# Serial_final_rev01.net
KiCad netlist of a schematic drawn in EAGLE
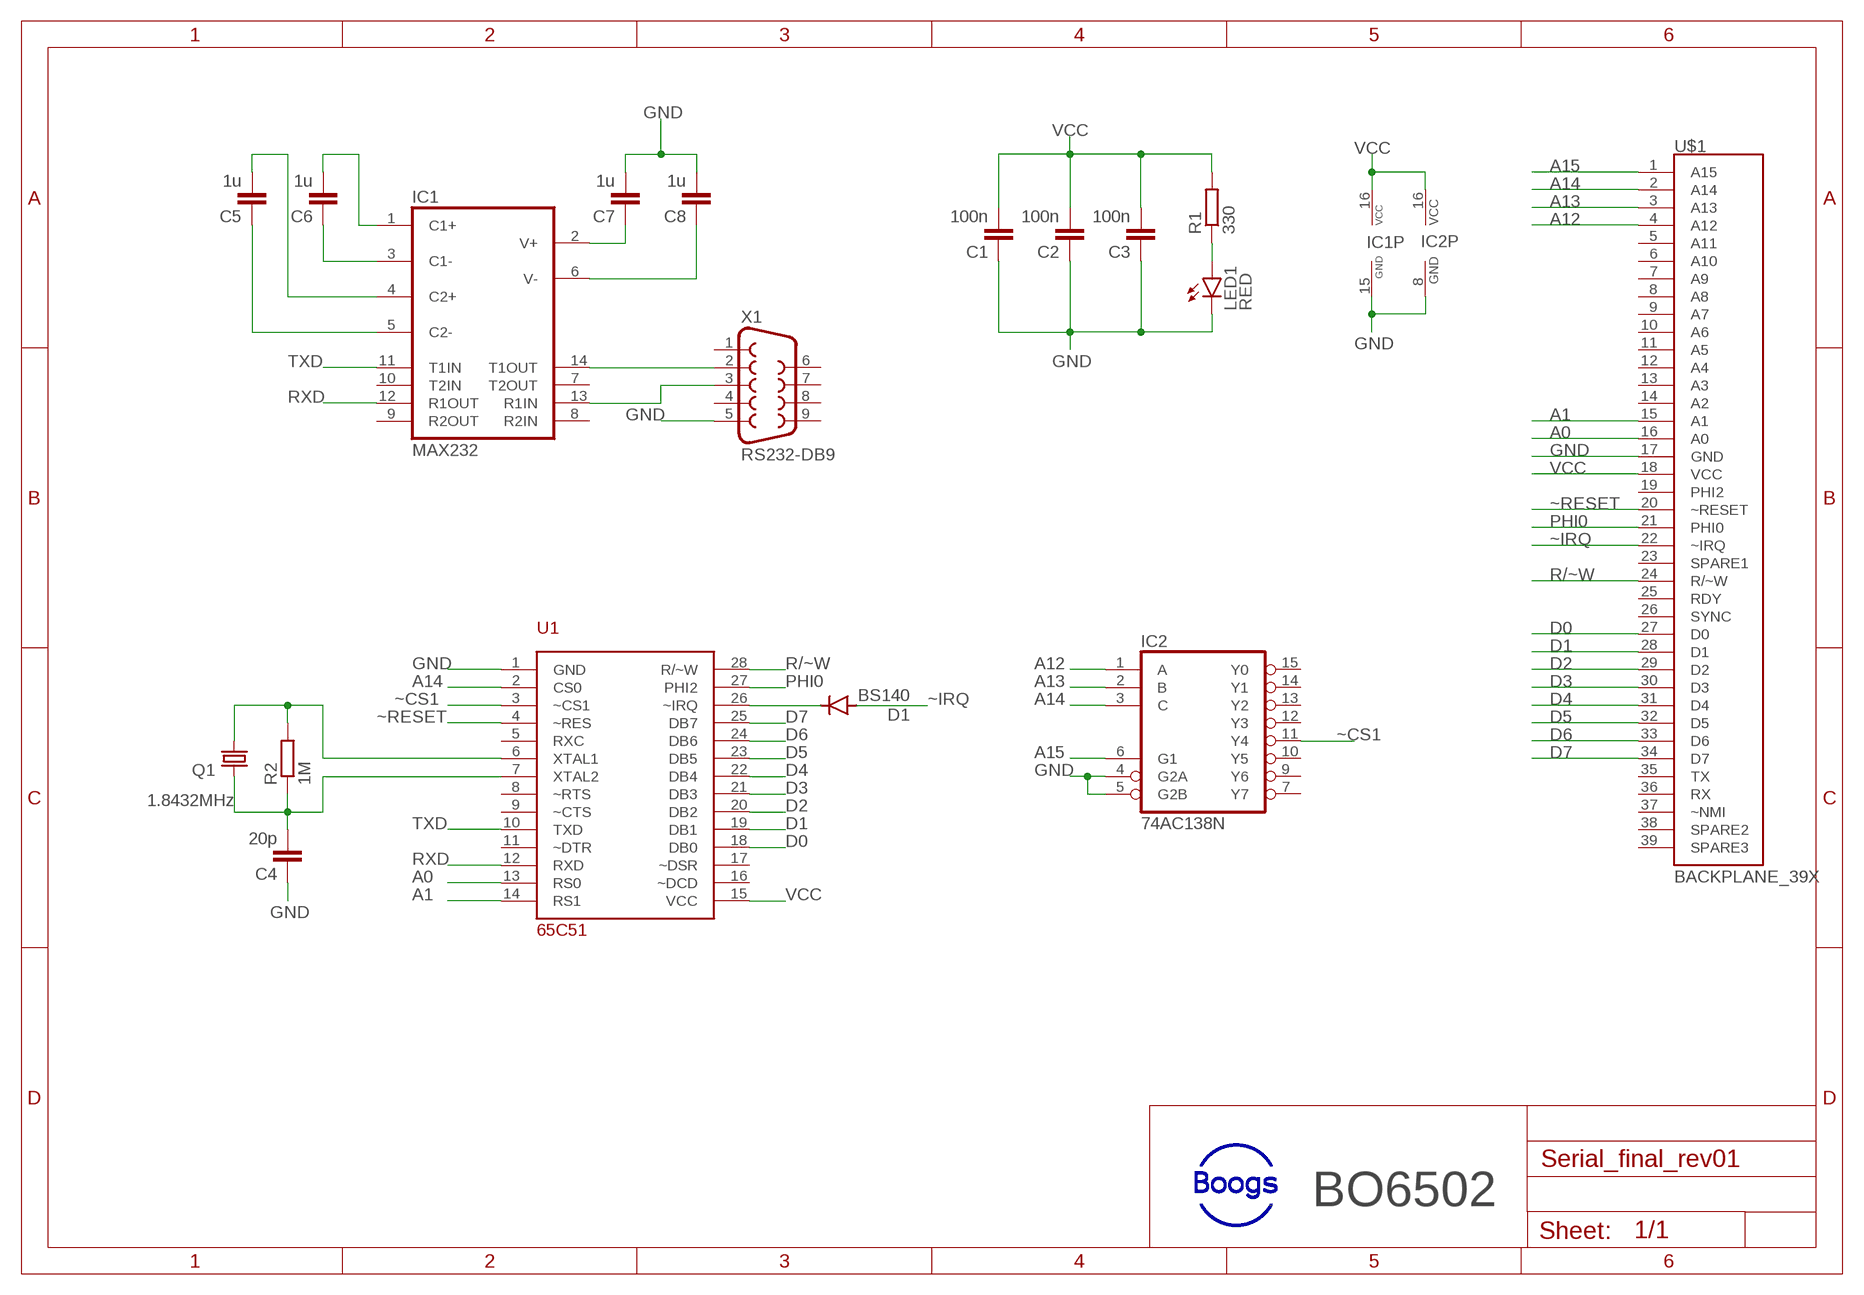
[diagram p0: schematic, sheet 1]

(export (version "E")
  (design (tool "Eeschema 10.0.6"))
  (components
    (comp (ref "C1")
      (value "100n")
      (footprint "eagle-import:C025-025X050")
      (libsource (lib "eagle-import") (part "C-EU025-025X050"))
    )
    (comp (ref "C2")
      (value "100n")
      (footprint "eagle-import:C025-025X050")
      (libsource (lib "eagle-import") (part "C-EU025-025X050"))
    )
    (comp (ref "C3")
      (value "100n")
      (footprint "eagle-import:C025-025X050")
      (libsource (lib "eagle-import") (part "C-EU025-025X050"))
    )
    (comp (ref "C4")
      (value "20p")
      (footprint "eagle-import:C025-025X050")
      (libsource (lib "eagle-import") (part "C-EU025-025X050"))
    )
    (comp (ref "C5")
      (value "1u")
      (footprint "eagle-import:C050-025X075")
      (libsource (lib "eagle-import") (part "C-EU050-025X075"))
    )
    (comp (ref "C6")
      (value "1u")
      (footprint "eagle-import:C050-025X075")
      (libsource (lib "eagle-import") (part "C-EU050-025X075"))
    )
    (comp (ref "C7")
      (value "1u")
      (footprint "eagle-import:C050-025X075")
      (libsource (lib "eagle-import") (part "C-EU050-025X075"))
    )
    (comp (ref "C8")
      (value "1u")
      (footprint "eagle-import:C050-025X075")
      (libsource (lib "eagle-import") (part "C-EU050-025X075"))
    )
    (comp (ref "D1")
      (value "BS140")
      (footprint "eagle-import:DO41-10")
      (libsource (lib "eagle-import") (part "1N4004"))
    )
    (comp (ref "IC1")
      (value "MAX232")
      (footprint "eagle-import:DIL16")
      (fields (field (name "MF") "MAXIM") (field (name "MPN") "MAX232ACPE+"))
      (libsource (lib "eagle-import") (part "MAX232"))
    )
    (comp (ref "IC2")
      (value "74AC138N")
      (footprint "eagle-import:DIL16")
      (libsource (lib "eagle-import") (part "74138NAC"))
    )
    (comp (ref "LED1")
      (value "RED")
      (footprint "eagle-import:LED5MM")
      (libsource (lib "eagle-import") (part "LED5MM"))
    )
    (comp (ref "Q1")
      (value "1.8432MHz")
      (footprint "eagle-import:HC49_S")
      (libsource (lib "eagle-import") (part "CRYSTALHC49S"))
    )
    (comp (ref "R1")
      (value "330")
      (footprint "eagle-import:0207_10")
      (libsource (lib "eagle-import") (part "R-EU_0207/10"))
    )
    (comp (ref "R2")
      (value "1M")
      (footprint "eagle-import:0207_10")
      (libsource (lib "eagle-import") (part "R-EU_0207/10"))
    )
    (comp (ref "U$1")
      (value "BACKPLANE_39X")
      (footprint "eagle-import:BP_39X")
      (fields (field (name "A15") "A15"))
      (libsource (lib "eagle-import") (part "BACKPLANE_39X"))
    )
    (comp (ref "U1")
      (value "65C51")
      (footprint "eagle-import:DIL28")
      (libsource (lib "eagle-import") (part "65C51"))
    )
    (comp (ref "X1")
      (value "RS232-DB9")
      (footprint "eagle-import:F09HP")
      (libsource (lib "eagle-import") (part "F09HP"))
    )
  )
  (nets
    (net (code "1") (name "/A0") (class "Default")
      (node (ref "U$1") (pin "16") (pinfunction "A0_16") (pintype "bidirectional"))
      (node (ref "U1") (pin "13") (pinfunction "RS0_13") (pintype "bidirectional"))
    )
    (net (code "2") (name "/A1") (class "Default")
      (node (ref "U$1") (pin "15") (pinfunction "A1_15") (pintype "bidirectional"))
      (node (ref "U1") (pin "14") (pinfunction "RS1_14") (pintype "bidirectional"))
    )
    (net (code "3") (name "/A12") (class "Default")
      (node (ref "IC2") (pin "1") (pinfunction "A_1") (pintype "input"))
      (node (ref "U$1") (pin "4") (pinfunction "A12_4") (pintype "bidirectional"))
    )
    (net (code "4") (name "/A13") (class "Default")
      (node (ref "IC2") (pin "2") (pinfunction "B_2") (pintype "input"))
      (node (ref "U$1") (pin "3") (pinfunction "A13_3") (pintype "bidirectional"))
    )
    (net (code "5") (name "/A14") (class "Default")
      (node (ref "IC2") (pin "3") (pinfunction "C_3") (pintype "input"))
      (node (ref "U$1") (pin "2") (pinfunction "A14_2") (pintype "bidirectional"))
      (node (ref "U1") (pin "2") (pinfunction "CS0_2") (pintype "bidirectional"))
    )
    (net (code "6") (name "/A15") (class "Default")
      (node (ref "IC2") (pin "6") (pinfunction "G1_6") (pintype "input"))
      (node (ref "U$1") (pin "1") (pinfunction "A15_1") (pintype "bidirectional"))
    )
    (net (code "7") (name "/D0") (class "Default")
      (node (ref "U$1") (pin "27") (pinfunction "D0_27") (pintype "bidirectional"))
      (node (ref "U1") (pin "18") (pinfunction "DB0_18") (pintype "bidirectional"))
    )
    (net (code "8") (name "/D1") (class "Default")
      (node (ref "U$1") (pin "28") (pinfunction "D1_28") (pintype "bidirectional"))
      (node (ref "U1") (pin "19") (pinfunction "DB1_19") (pintype "bidirectional"))
    )
    (net (code "9") (name "/D2") (class "Default")
      (node (ref "U$1") (pin "29") (pinfunction "D2_29") (pintype "bidirectional"))
      (node (ref "U1") (pin "20") (pinfunction "DB2_20") (pintype "bidirectional"))
    )
    (net (code "10") (name "/D3") (class "Default")
      (node (ref "U$1") (pin "30") (pinfunction "D3_30") (pintype "bidirectional"))
      (node (ref "U1") (pin "21") (pinfunction "DB3_21") (pintype "bidirectional"))
    )
    (net (code "11") (name "/D4") (class "Default")
      (node (ref "U$1") (pin "31") (pinfunction "D4_31") (pintype "bidirectional"))
      (node (ref "U1") (pin "22") (pinfunction "DB4_22") (pintype "bidirectional"))
    )
    (net (code "12") (name "/D5") (class "Default")
      (node (ref "U$1") (pin "32") (pinfunction "D5_32") (pintype "bidirectional"))
      (node (ref "U1") (pin "23") (pinfunction "DB5_23") (pintype "bidirectional"))
    )
    (net (code "13") (name "/D6") (class "Default")
      (node (ref "U$1") (pin "33") (pinfunction "D6_33") (pintype "bidirectional"))
      (node (ref "U1") (pin "24") (pinfunction "DB6_24") (pintype "bidirectional"))
    )
    (net (code "14") (name "/D7") (class "Default")
      (node (ref "U$1") (pin "34") (pinfunction "D7_34") (pintype "bidirectional"))
      (node (ref "U1") (pin "25") (pinfunction "DB7_25") (pintype "bidirectional"))
    )
    (net (code "15") (name "/GND") (class "Default")
      (node (ref "C1") (pin "1") (pinfunction "1_1") (pintype "passive"))
      (node (ref "C2") (pin "1") (pinfunction "1_1") (pintype "passive"))
      (node (ref "C3") (pin "1") (pinfunction "1_1") (pintype "passive"))
      (node (ref "C4") (pin "1") (pinfunction "1_1") (pintype "passive"))
      (node (ref "C7") (pin "2") (pinfunction "2_2") (pintype "passive"))
      (node (ref "C8") (pin "2") (pinfunction "2_2") (pintype "passive"))
      (node (ref "IC1") (pin "15") (pinfunction "GND_15") (pintype "power_in"))
      (node (ref "IC2") (pin "4") (pinfunction "G2A_4") (pintype "input"))
      (node (ref "IC2") (pin "5") (pinfunction "G2B_5") (pintype "input"))
      (node (ref "IC2") (pin "8") (pinfunction "GND_8") (pintype "power_in"))
      (node (ref "LED1") (pin "K") (pinfunction "C_K") (pintype "passive"))
      (node (ref "U$1") (pin "17") (pinfunction "GND_17") (pintype "bidirectional"))
      (node (ref "U1") (pin "1") (pinfunction "GND_1") (pintype "bidirectional"))
      (node (ref "X1") (pin "5") (pinfunction "5_5") (pintype "passive"))
    )
    (net (code "16") (name "/PHI0") (class "Default")
      (node (ref "U$1") (pin "21") (pinfunction "PHI0_21") (pintype "bidirectional"))
      (node (ref "U1") (pin "27") (pinfunction "PHI2_27") (pintype "bidirectional"))
    )
    (net (code "17") (name "/RXD") (class "Default")
      (node (ref "IC1") (pin "12") (pinfunction "R1OUT_12") (pintype "output"))
      (node (ref "U1") (pin "12") (pinfunction "RXD_12") (pintype "bidirectional"))
    )
    (net (code "18") (name "/R{slash}~{W}") (class "Default")
      (node (ref "U$1") (pin "24") (pinfunction "R/~{W}_24") (pintype "bidirectional"))
      (node (ref "U1") (pin "28") (pinfunction "R/~{W}_28") (pintype "bidirectional"))
    )
    (net (code "19") (name "/TXD") (class "Default")
      (node (ref "IC1") (pin "11") (pinfunction "T1IN_11") (pintype "input"))
      (node (ref "U1") (pin "10") (pinfunction "TXD_10") (pintype "bidirectional"))
    )
    (net (code "20") (name "/VCC") (class "Default")
      (node (ref "C1") (pin "2") (pinfunction "2_2") (pintype "passive"))
      (node (ref "C2") (pin "2") (pinfunction "2_2") (pintype "passive"))
      (node (ref "C3") (pin "2") (pinfunction "2_2") (pintype "passive"))
      (node (ref "IC1") (pin "16") (pinfunction "VCC_16") (pintype "power_in"))
      (node (ref "IC2") (pin "16") (pinfunction "VCC_16") (pintype "power_in"))
      (node (ref "R1") (pin "2") (pinfunction "2_2") (pintype "passive"))
      (node (ref "U$1") (pin "18") (pinfunction "VCC_18") (pintype "bidirectional"))
      (node (ref "U1") (pin "15") (pinfunction "VCC_15") (pintype "bidirectional"))
    )
    (net (code "21") (name "/~{CS1}") (class "Default")
      (node (ref "IC2") (pin "11") (pinfunction "Y4_11") (pintype "output"))
      (node (ref "U1") (pin "3") (pinfunction "~{CS1}_3") (pintype "bidirectional"))
    )
    (net (code "22") (name "/~{IRQ}") (class "Default")
      (node (ref "D1") (pin "A") (pinfunction "A_A") (pintype "passive"))
      (node (ref "U$1") (pin "22") (pinfunction "~{IRQ}_22") (pintype "bidirectional"))
    )
    (net (code "23") (name "/~{RESET}") (class "Default")
      (node (ref "U$1") (pin "20") (pinfunction "~{RESET}_20") (pintype "bidirectional"))
      (node (ref "U1") (pin "4") (pinfunction "~{RES}_4") (pintype "bidirectional"))
    )
    (net (code "24") (name "Net-(IC1A-C1+)") (class "Default")
      (node (ref "C6") (pin "2") (pinfunction "2_2") (pintype "passive"))
      (node (ref "IC1") (pin "1") (pinfunction "C1+_1") (pintype "bidirectional"))
    )
    (net (code "25") (name "Net-(IC1A-C1-)") (class "Default")
      (node (ref "C6") (pin "1") (pinfunction "1_1") (pintype "passive"))
      (node (ref "IC1") (pin "3") (pinfunction "C1-_3") (pintype "bidirectional"))
    )
    (net (code "26") (name "Net-(IC1A-C2+)") (class "Default")
      (node (ref "C5") (pin "2") (pinfunction "2_2") (pintype "passive"))
      (node (ref "IC1") (pin "4") (pinfunction "C2+_4") (pintype "bidirectional"))
    )
    (net (code "27") (name "Net-(IC1A-C2-)") (class "Default")
      (node (ref "C5") (pin "1") (pinfunction "1_1") (pintype "passive"))
      (node (ref "IC1") (pin "5") (pinfunction "C2-_5") (pintype "bidirectional"))
    )
    (net (code "28") (name "Net-(IC1A-R1IN)") (class "Default")
      (node (ref "IC1") (pin "13") (pinfunction "R1IN_13") (pintype "input"))
      (node (ref "X1") (pin "3") (pinfunction "3_3") (pintype "passive"))
    )
    (net (code "29") (name "Net-(IC1A-T1OUT)") (class "Default")
      (node (ref "IC1") (pin "14") (pinfunction "T1OUT_14") (pintype "output"))
      (node (ref "X1") (pin "2") (pinfunction "2_2") (pintype "passive"))
    )
    (net (code "30") (name "Net-(IC1A-V+)") (class "Default")
      (node (ref "C7") (pin "1") (pinfunction "1_1") (pintype "passive"))
      (node (ref "IC1") (pin "2") (pinfunction "V+_2") (pintype "bidirectional"))
    )
    (net (code "31") (name "Net-(IC1A-V-)") (class "Default")
      (node (ref "C8") (pin "1") (pinfunction "1_1") (pintype "passive"))
      (node (ref "IC1") (pin "6") (pinfunction "V-_6") (pintype "bidirectional"))
    )
    (net (code "32") (name "Net-(LED1-PadA)") (class "Default")
      (node (ref "LED1") (pin "A") (pinfunction "A_A") (pintype "passive"))
      (node (ref "R1") (pin "1") (pinfunction "1_1") (pintype "passive"))
    )
    (net (code "33") (name "Net-(U1-XTAL1)") (class "Default")
      (node (ref "Q1") (pin "2") (pinfunction "2_2") (pintype "passive"))
      (node (ref "R2") (pin "2") (pinfunction "2_2") (pintype "passive"))
      (node (ref "U1") (pin "6") (pinfunction "XTAL1_6") (pintype "bidirectional"))
    )
    (net (code "34") (name "Net-(U1-XTAL2)") (class "Default")
      (node (ref "C4") (pin "2") (pinfunction "2_2") (pintype "passive"))
      (node (ref "Q1") (pin "1") (pinfunction "1_1") (pintype "passive"))
      (node (ref "R2") (pin "1") (pinfunction "1_1") (pintype "passive"))
      (node (ref "U1") (pin "7") (pinfunction "XTAL2_7") (pintype "bidirectional"))
    )
    (net (code "35") (name "Net-(U1-~{IRQ})") (class "Default")
      (node (ref "D1") (pin "C") (pinfunction "C_C") (pintype "passive"))
      (node (ref "U1") (pin "26") (pinfunction "~{IRQ}_26") (pintype "bidirectional"))
    )
    (net (code "36") (name "unconnected-(IC1A-R2IN-Pad8)") (class "Default")
      (node (ref "IC1") (pin "8") (pinfunction "R2IN_8") (pintype "input"))
    )
    (net (code "37") (name "unconnected-(IC1A-R2OUT-Pad9)") (class "Default")
      (node (ref "IC1") (pin "9") (pinfunction "R2OUT_9") (pintype "output"))
    )
    (net (code "38") (name "unconnected-(IC1A-T2IN-Pad10)") (class "Default")
      (node (ref "IC1") (pin "10") (pinfunction "T2IN_10") (pintype "input"))
    )
    (net (code "39") (name "unconnected-(IC1A-T2OUT-Pad7)") (class "Default")
      (node (ref "IC1") (pin "7") (pinfunction "T2OUT_7") (pintype "output"))
    )
    (net (code "40") (name "unconnected-(IC2A-Y0-Pad15)") (class "Default")
      (node (ref "IC2") (pin "15") (pinfunction "Y0_15") (pintype "output"))
    )
    (net (code "41") (name "unconnected-(IC2A-Y1-Pad14)") (class "Default")
      (node (ref "IC2") (pin "14") (pinfunction "Y1_14") (pintype "output"))
    )
    (net (code "42") (name "unconnected-(IC2A-Y2-Pad13)") (class "Default")
      (node (ref "IC2") (pin "13") (pinfunction "Y2_13") (pintype "output"))
    )
    (net (code "43") (name "unconnected-(IC2A-Y3-Pad12)") (class "Default")
      (node (ref "IC2") (pin "12") (pinfunction "Y3_12") (pintype "output"))
    )
    (net (code "44") (name "unconnected-(IC2A-Y5-Pad10)") (class "Default")
      (node (ref "IC2") (pin "10") (pinfunction "Y5_10") (pintype "output"))
    )
    (net (code "45") (name "unconnected-(IC2A-Y6-Pad9)") (class "Default")
      (node (ref "IC2") (pin "9") (pinfunction "Y6_9") (pintype "output"))
    )
    (net (code "46") (name "unconnected-(IC2A-Y7-Pad7)") (class "Default")
      (node (ref "IC2") (pin "7") (pinfunction "Y7_7") (pintype "output"))
    )
    (net (code "47") (name "unconnected-(U$1-A2-Pad14)") (class "Default")
      (node (ref "U$1") (pin "14") (pinfunction "A2_14") (pintype "bidirectional"))
    )
    (net (code "48") (name "unconnected-(U$1-A3-Pad13)") (class "Default")
      (node (ref "U$1") (pin "13") (pinfunction "A3_13") (pintype "bidirectional"))
    )
    (net (code "49") (name "unconnected-(U$1-A4-Pad12)") (class "Default")
      (node (ref "U$1") (pin "12") (pinfunction "A4_12") (pintype "bidirectional"))
    )
    (net (code "50") (name "unconnected-(U$1-A5-Pad11)") (class "Default")
      (node (ref "U$1") (pin "11") (pinfunction "A5_11") (pintype "bidirectional"))
    )
    (net (code "51") (name "unconnected-(U$1-A6-Pad10)") (class "Default")
      (node (ref "U$1") (pin "10") (pinfunction "A6_10") (pintype "bidirectional"))
    )
    (net (code "52") (name "unconnected-(U$1-A7-Pad9)") (class "Default")
      (node (ref "U$1") (pin "9") (pinfunction "A7_9") (pintype "bidirectional"))
    )
    (net (code "53") (name "unconnected-(U$1-A8-Pad8)") (class "Default")
      (node (ref "U$1") (pin "8") (pinfunction "A8_8") (pintype "bidirectional"))
    )
    (net (code "54") (name "unconnected-(U$1-A9-Pad7)") (class "Default")
      (node (ref "U$1") (pin "7") (pinfunction "A9_7") (pintype "bidirectional"))
    )
    (net (code "55") (name "unconnected-(U$1-A10-Pad6)") (class "Default")
      (node (ref "U$1") (pin "6") (pinfunction "A10_6") (pintype "bidirectional"))
    )
    (net (code "56") (name "unconnected-(U$1-A11-Pad5)") (class "Default")
      (node (ref "U$1") (pin "5") (pinfunction "A11_5") (pintype "bidirectional"))
    )
    (net (code "57") (name "unconnected-(U$1-PHI2-Pad19)") (class "Default")
      (node (ref "U$1") (pin "19") (pinfunction "PHI2_19") (pintype "bidirectional"))
    )
    (net (code "58") (name "unconnected-(U$1-RDY-Pad25)") (class "Default")
      (node (ref "U$1") (pin "25") (pinfunction "RDY_25") (pintype "bidirectional"))
    )
    (net (code "59") (name "unconnected-(U$1-RX-Pad36)") (class "Default")
      (node (ref "U$1") (pin "36") (pinfunction "RX_36") (pintype "bidirectional"))
    )
    (net (code "60") (name "unconnected-(U$1-SPARE1-Pad23)") (class "Default")
      (node (ref "U$1") (pin "23") (pinfunction "SPARE1_23") (pintype "bidirectional"))
    )
    (net (code "61") (name "unconnected-(U$1-SPARE2-Pad38)") (class "Default")
      (node (ref "U$1") (pin "38") (pinfunction "SPARE2_38") (pintype "bidirectional"))
    )
    (net (code "62") (name "unconnected-(U$1-SPARE3-Pad39)") (class "Default")
      (node (ref "U$1") (pin "39") (pinfunction "SPARE3_39") (pintype "bidirectional"))
    )
    (net (code "63") (name "unconnected-(U$1-SYNC-Pad26)") (class "Default")
      (node (ref "U$1") (pin "26") (pinfunction "SYNC_26") (pintype "bidirectional"))
    )
    (net (code "64") (name "unconnected-(U$1-TX-Pad35)") (class "Default")
      (node (ref "U$1") (pin "35") (pinfunction "TX_35") (pintype "bidirectional"))
    )
    (net (code "65") (name "unconnected-(U$1-~{NMI}-Pad37)") (class "Default")
      (node (ref "U$1") (pin "37") (pinfunction "~{NMI}_37") (pintype "bidirectional"))
    )
    (net (code "66") (name "unconnected-(U1-RXC-Pad5)") (class "Default")
      (node (ref "U1") (pin "5") (pinfunction "RXC_5") (pintype "bidirectional"))
    )
    (net (code "67") (name "unconnected-(U1-~{CTS}-Pad9)") (class "Default")
      (node (ref "U1") (pin "9") (pinfunction "~{CTS}_9") (pintype "bidirectional"))
    )
    (net (code "68") (name "unconnected-(U1-~{DCD}-Pad16)") (class "Default")
      (node (ref "U1") (pin "16") (pinfunction "~{DCD}_16") (pintype "bidirectional"))
    )
    (net (code "69") (name "unconnected-(U1-~{DSR}-Pad17)") (class "Default")
      (node (ref "U1") (pin "17") (pinfunction "~{DSR}_17") (pintype "bidirectional"))
    )
    (net (code "70") (name "unconnected-(U1-~{DTR}-Pad11)") (class "Default")
      (node (ref "U1") (pin "11") (pinfunction "~{DTR}_11") (pintype "bidirectional"))
    )
    (net (code "71") (name "unconnected-(U1-~{RTS}-Pad8)") (class "Default")
      (node (ref "U1") (pin "8") (pinfunction "~{RTS}_8") (pintype "bidirectional"))
    )
    (net (code "72") (name "unconnected-(X1-Pad1)") (class "Default")
      (node (ref "X1") (pin "1") (pinfunction "1_1") (pintype "passive"))
    )
    (net (code "73") (name "unconnected-(X1-Pad4)") (class "Default")
      (node (ref "X1") (pin "4") (pinfunction "4_4") (pintype "passive"))
    )
    (net (code "74") (name "unconnected-(X1-Pad6)") (class "Default")
      (node (ref "X1") (pin "6") (pinfunction "6_6") (pintype "passive"))
    )
    (net (code "75") (name "unconnected-(X1-Pad7)") (class "Default")
      (node (ref "X1") (pin "7") (pinfunction "7_7") (pintype "passive"))
    )
    (net (code "76") (name "unconnected-(X1-Pad8)") (class "Default")
      (node (ref "X1") (pin "8") (pinfunction "8_8") (pintype "passive"))
    )
    (net (code "77") (name "unconnected-(X1-Pad9)") (class "Default")
      (node (ref "X1") (pin "9") (pinfunction "9_9") (pintype "passive"))
    )
  )
)
